# B198A.net
KiCad netlist of a schematic drawn in EAGLE
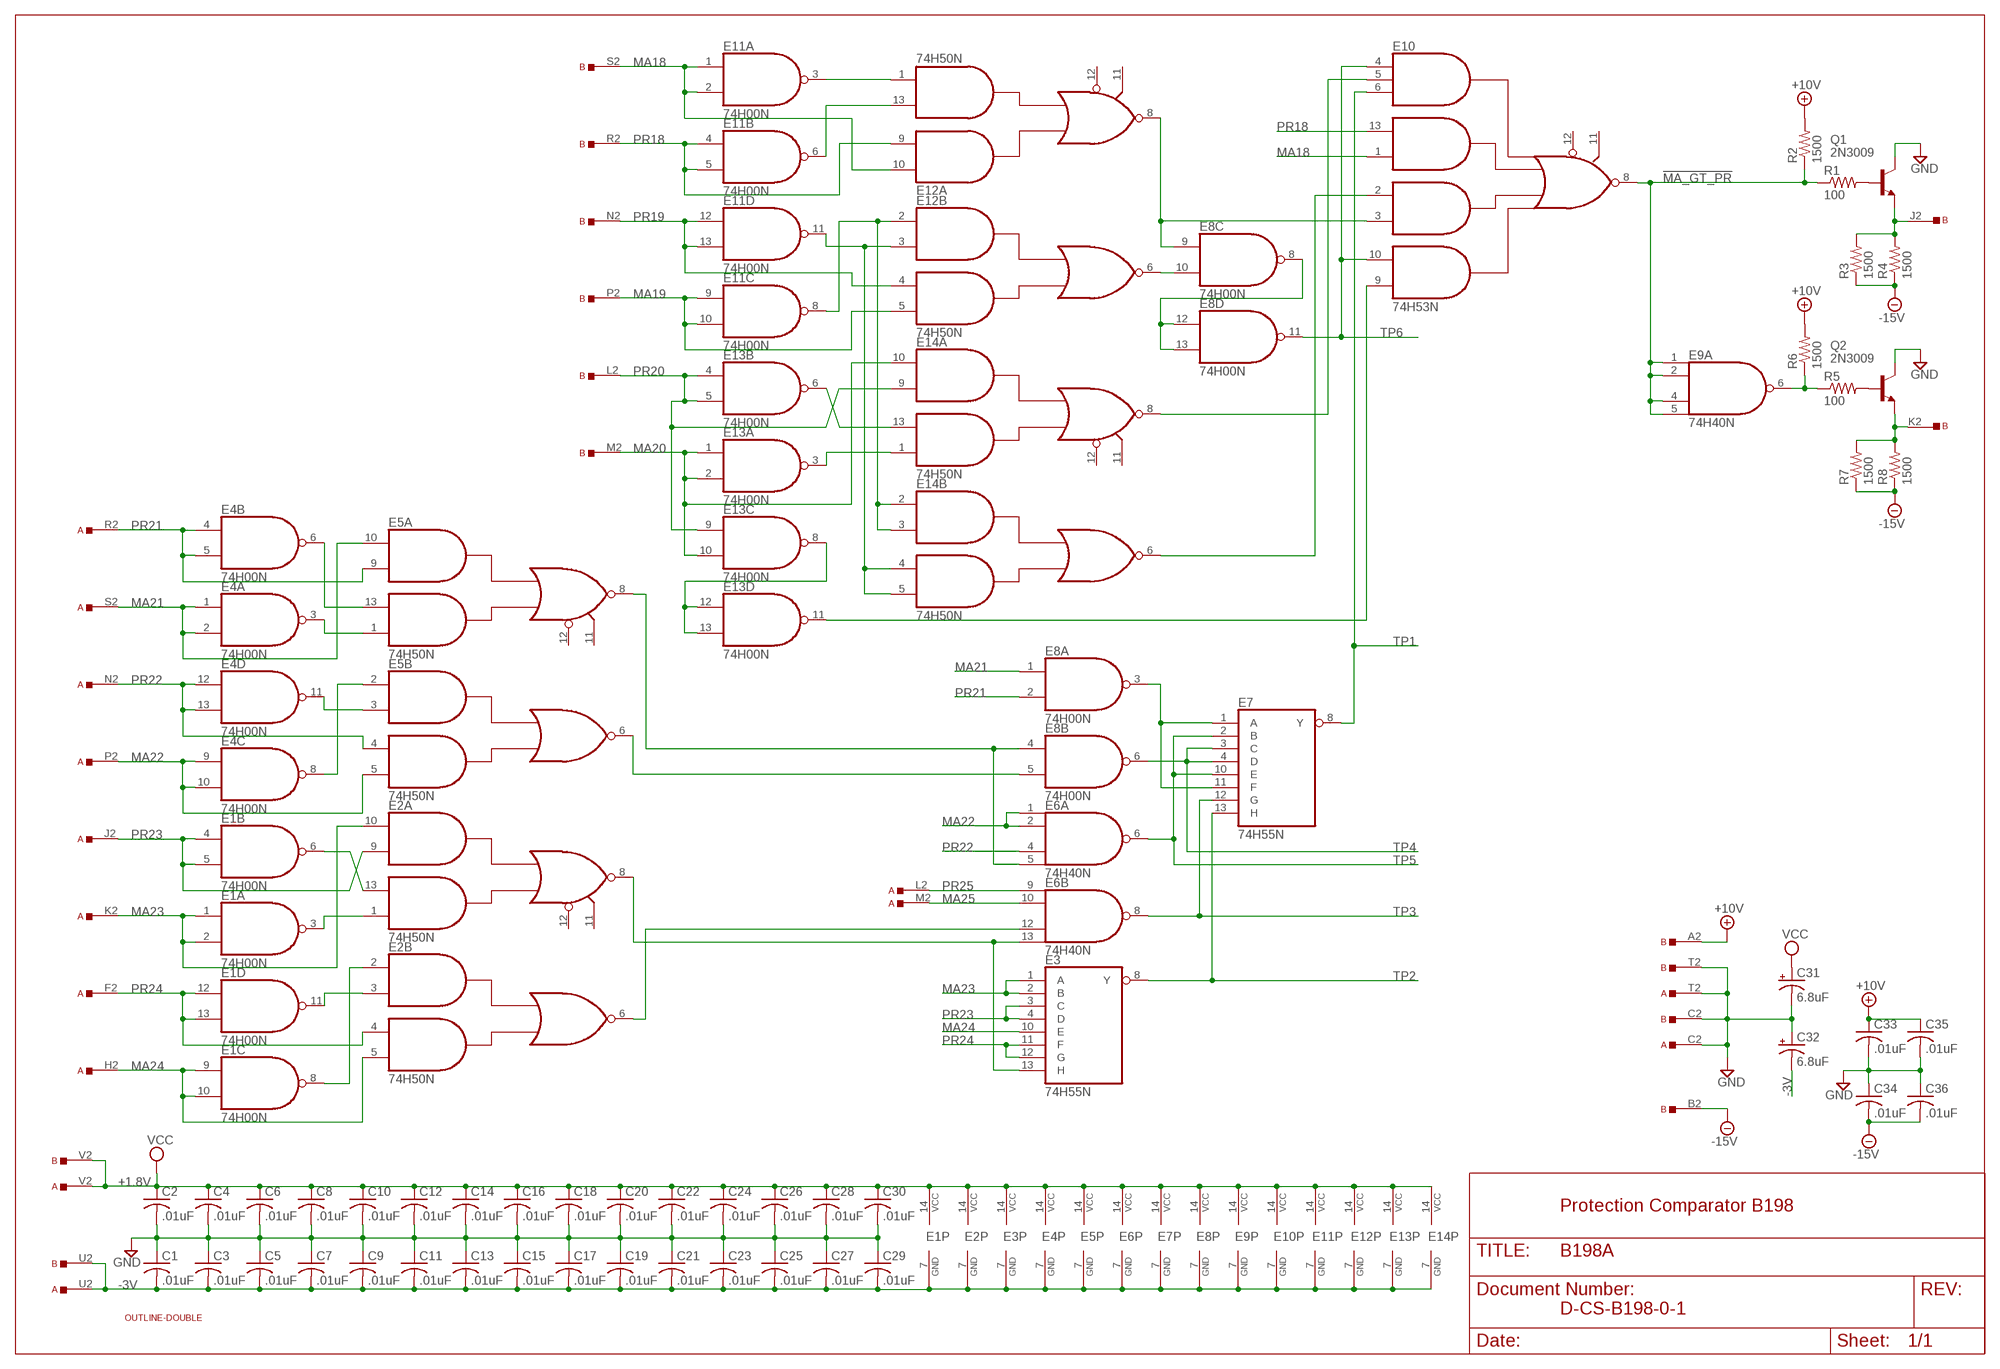
[diagram p0: schematic, sheet 1]

(export (version "E")
  (design (tool "Eeschema 10.0.6"))
  (components
    (comp (ref "A")
      (value "SS-TOP")
      (footprint "eagle-import:EDGE-CON1")
      (libsource (lib "eagle-import") (part "SS-TOP"))
    )
    (comp (ref "B")
      (value "SS-TOP")
      (footprint "eagle-import:EDGE-CON1")
      (libsource (lib "eagle-import") (part "SS-TOP"))
    )
    (comp (ref "C1")
      (value ".01uF")
      (footprint "eagle-import:C063-025X075")
      (libsource (lib "eagle-import") (part "C-US"))
    )
    (comp (ref "C2")
      (value ".01uF")
      (footprint "eagle-import:C063-025X075")
      (libsource (lib "eagle-import") (part "C-US"))
    )
    (comp (ref "C3")
      (value ".01uF")
      (footprint "eagle-import:C063-025X075")
      (libsource (lib "eagle-import") (part "C-US"))
    )
    (comp (ref "C4")
      (value ".01uF")
      (footprint "eagle-import:C063-025X075")
      (libsource (lib "eagle-import") (part "C-US"))
    )
    (comp (ref "C5")
      (value ".01uF")
      (footprint "eagle-import:C063-025X075")
      (libsource (lib "eagle-import") (part "C-US"))
    )
    (comp (ref "C6")
      (value ".01uF")
      (footprint "eagle-import:C063-025X075")
      (libsource (lib "eagle-import") (part "C-US"))
    )
    (comp (ref "C7")
      (value ".01uF")
      (footprint "eagle-import:C063-025X075")
      (libsource (lib "eagle-import") (part "C-US"))
    )
    (comp (ref "C8")
      (value ".01uF")
      (footprint "eagle-import:C063-025X075")
      (libsource (lib "eagle-import") (part "C-US"))
    )
    (comp (ref "C9")
      (value ".01uF")
      (footprint "eagle-import:C063-025X075")
      (libsource (lib "eagle-import") (part "C-US"))
    )
    (comp (ref "C10")
      (value ".01uF")
      (footprint "eagle-import:C063-025X075")
      (libsource (lib "eagle-import") (part "C-US"))
    )
    (comp (ref "C11")
      (value ".01uF")
      (footprint "eagle-import:C063-025X075")
      (libsource (lib "eagle-import") (part "C-US"))
    )
    (comp (ref "C12")
      (value ".01uF")
      (footprint "eagle-import:C063-025X075")
      (libsource (lib "eagle-import") (part "C-US"))
    )
    (comp (ref "C13")
      (value ".01uF")
      (footprint "eagle-import:C063-025X075")
      (libsource (lib "eagle-import") (part "C-US"))
    )
    (comp (ref "C14")
      (value ".01uF")
      (footprint "eagle-import:C063-025X075")
      (libsource (lib "eagle-import") (part "C-US"))
    )
    (comp (ref "C15")
      (value ".01uF")
      (footprint "eagle-import:C063-025X075")
      (libsource (lib "eagle-import") (part "C-US"))
    )
    (comp (ref "C16")
      (value ".01uF")
      (footprint "eagle-import:C063-025X075")
      (libsource (lib "eagle-import") (part "C-US"))
    )
    (comp (ref "C17")
      (value ".01uF")
      (footprint "eagle-import:C063-025X075")
      (libsource (lib "eagle-import") (part "C-US"))
    )
    (comp (ref "C18")
      (value ".01uF")
      (footprint "eagle-import:C063-025X075")
      (libsource (lib "eagle-import") (part "C-US"))
    )
    (comp (ref "C19")
      (value ".01uF")
      (footprint "eagle-import:C063-025X075")
      (libsource (lib "eagle-import") (part "C-US"))
    )
    (comp (ref "C20")
      (value ".01uF")
      (footprint "eagle-import:C063-025X075")
      (libsource (lib "eagle-import") (part "C-US"))
    )
    (comp (ref "C21")
      (value ".01uF")
      (footprint "eagle-import:C063-025X075")
      (libsource (lib "eagle-import") (part "C-US"))
    )
    (comp (ref "C22")
      (value ".01uF")
      (footprint "eagle-import:C063-025X075")
      (libsource (lib "eagle-import") (part "C-US"))
    )
    (comp (ref "C23")
      (value ".01uF")
      (footprint "eagle-import:C063-025X075")
      (libsource (lib "eagle-import") (part "C-US"))
    )
    (comp (ref "C24")
      (value ".01uF")
      (footprint "eagle-import:C063-025X075")
      (libsource (lib "eagle-import") (part "C-US"))
    )
    (comp (ref "C25")
      (value ".01uF")
      (footprint "eagle-import:C063-025X075")
      (libsource (lib "eagle-import") (part "C-US"))
    )
    (comp (ref "C26")
      (value ".01uF")
      (footprint "eagle-import:C063-025X075")
      (libsource (lib "eagle-import") (part "C-US"))
    )
    (comp (ref "C27")
      (value ".01uF")
      (footprint "eagle-import:C063-025X075")
      (libsource (lib "eagle-import") (part "C-US"))
    )
    (comp (ref "C28")
      (value ".01uF")
      (footprint "eagle-import:C063-025X075")
      (libsource (lib "eagle-import") (part "C-US"))
    )
    (comp (ref "C29")
      (value ".01uF")
      (footprint "eagle-import:C063-025X075")
      (libsource (lib "eagle-import") (part "C-US"))
    )
    (comp (ref "C30")
      (value ".01uF")
      (footprint "eagle-import:C063-025X075")
      (libsource (lib "eagle-import") (part "C-US"))
    )
    (comp (ref "C31")
      (value "6.8uF")
      (footprint "eagle-import:E15-5")
      (libsource (lib "eagle-import") (part "CPOL-USE15-5AXIAL"))
    )
    (comp (ref "C32")
      (value "6.8uF")
      (footprint "eagle-import:E15-5")
      (libsource (lib "eagle-import") (part "CPOL-USE15-5AXIAL"))
    )
    (comp (ref "C33")
      (value ".01uF")
      (footprint "eagle-import:C063-025X075")
      (libsource (lib "eagle-import") (part "C-US"))
    )
    (comp (ref "C34")
      (value ".01uF")
      (footprint "eagle-import:C063-025X075")
      (libsource (lib "eagle-import") (part "C-US"))
    )
    (comp (ref "C35")
      (value ".01uF")
      (footprint "eagle-import:C063-025X075")
      (libsource (lib "eagle-import") (part "C-US"))
    )
    (comp (ref "C36")
      (value ".01uF")
      (footprint "eagle-import:C063-025X075")
      (libsource (lib "eagle-import") (part "C-US"))
    )
    (comp (ref "E1")
      (value "74H00N")
      (footprint "eagle-import:DIL14")
      (libsource (lib "eagle-import") (part "7400NS"))
    )
    (comp (ref "E2")
      (value "74H50N")
      (footprint "eagle-import:DIL14")
      (libsource (lib "eagle-import") (part "7450N"))
    )
    (comp (ref "E3")
      (value "74H55N")
      (footprint "eagle-import:DIL14")
      (libsource (lib "eagle-import") (part "7455NLS"))
    )
    (comp (ref "E4")
      (value "74H00N")
      (footprint "eagle-import:DIL14")
      (libsource (lib "eagle-import") (part "7400NS"))
    )
    (comp (ref "E5")
      (value "74H50N")
      (footprint "eagle-import:DIL14")
      (libsource (lib "eagle-import") (part "7450N"))
    )
    (comp (ref "E6")
      (value "74H40N")
      (footprint "eagle-import:DIL14")
      (libsource (lib "eagle-import") (part "7440N"))
    )
    (comp (ref "E7")
      (value "74H55N")
      (footprint "eagle-import:DIL14")
      (libsource (lib "eagle-import") (part "7455NLS"))
    )
    (comp (ref "E8")
      (value "74H00N")
      (footprint "eagle-import:DIL14")
      (libsource (lib "eagle-import") (part "7400NS"))
    )
    (comp (ref "E9")
      (value "74H40N")
      (footprint "eagle-import:DIL14")
      (libsource (lib "eagle-import") (part "7440N"))
    )
    (comp (ref "E10")
      (value "74H53N")
      (footprint "eagle-import:DIL14")
      (libsource (lib "eagle-import") (part "74H53N"))
    )
    (comp (ref "E11")
      (value "74H00N")
      (footprint "eagle-import:DIL14")
      (libsource (lib "eagle-import") (part "7400NS"))
    )
    (comp (ref "E12")
      (value "74H50N")
      (footprint "eagle-import:DIL14")
      (libsource (lib "eagle-import") (part "7450N"))
    )
    (comp (ref "E13")
      (value "74H00N")
      (footprint "eagle-import:DIL14")
      (libsource (lib "eagle-import") (part "7400NS"))
    )
    (comp (ref "E14")
      (value "74H50N")
      (footprint "eagle-import:DIL14")
      (libsource (lib "eagle-import") (part "7450N"))
    )
    (comp (ref "Q1")
      (value "2N3009")
      (footprint "eagle-import:TO5")
      (libsource (lib "eagle-import") (part "-NPN-TO5"))
    )
    (comp (ref "Q2")
      (value "2N3009")
      (footprint "eagle-import:TO5")
      (libsource (lib "eagle-import") (part "-NPN-TO5"))
    )
    (comp (ref "R1")
      (value "100")
      (footprint "eagle-import:0207_10")
      (libsource (lib "eagle-import") (part "R-US_0207/10"))
    )
    (comp (ref "R2")
      (value "1500")
      (footprint "eagle-import:0207_10")
      (libsource (lib "eagle-import") (part "R-US_0207/10"))
    )
    (comp (ref "R3")
      (value "1500")
      (footprint "eagle-import:0207_10")
      (libsource (lib "eagle-import") (part "R-US_0207/10"))
    )
    (comp (ref "R4")
      (value "1500")
      (footprint "eagle-import:0207_10")
      (libsource (lib "eagle-import") (part "R-US_0207/10"))
    )
    (comp (ref "R5")
      (value "100")
      (footprint "eagle-import:0207_10")
      (libsource (lib "eagle-import") (part "R-US_0207/10"))
    )
    (comp (ref "R6")
      (value "1500")
      (footprint "eagle-import:0207_10")
      (libsource (lib "eagle-import") (part "R-US_0207/10"))
    )
    (comp (ref "R7")
      (value "1500")
      (footprint "eagle-import:0207_10")
      (libsource (lib "eagle-import") (part "R-US_0207/10"))
    )
    (comp (ref "R8")
      (value "1500")
      (footprint "eagle-import:0207_10")
      (libsource (lib "eagle-import") (part "R-US_0207/10"))
    )
    (comp (ref "U$1")
      (value "OUTLINE-DOUBLE")
      (footprint "eagle-import:DOUBLE")
      (libsource (lib "eagle-import") (part "OUTLINE-DOUBLE"))
    )
  )
  (nets
    (net (code "1") (name "+10V") (class "Default")
      (node (ref "B") (pin "A2") (pinfunction "P_A2") (pintype "passive"))
      (node (ref "C33") (pin "1") (pinfunction "1_1") (pintype "passive"))
      (node (ref "C35") (pin "1") (pinfunction "1_1") (pintype "passive"))
      (node (ref "R2") (pin "2") (pinfunction "2_2") (pintype "passive"))
      (node (ref "R6") (pin "2") (pinfunction "2_2") (pintype "passive"))
    )
    (net (code "2") (name "-15V") (class "Default")
      (node (ref "B") (pin "B2") (pinfunction "P_B2") (pintype "passive"))
      (node (ref "C34") (pin "2") (pinfunction "2_2") (pintype "passive"))
      (node (ref "C36") (pin "2") (pinfunction "2_2") (pintype "passive"))
      (node (ref "R3") (pin "1") (pinfunction "1_1") (pintype "passive"))
      (node (ref "R4") (pin "1") (pinfunction "1_1") (pintype "passive"))
      (node (ref "R7") (pin "1") (pinfunction "1_1") (pintype "passive"))
      (node (ref "R8") (pin "1") (pinfunction "1_1") (pintype "passive"))
    )
    (net (code "3") (name "/-3V") (class "Default")
      (node (ref "A") (pin "U2") (pinfunction "P_U2") (pintype "passive"))
      (node (ref "B") (pin "U2") (pinfunction "P_U2") (pintype "passive"))
      (node (ref "C1") (pin "2") (pinfunction "2_2") (pintype "passive"))
      (node (ref "C11") (pin "2") (pinfunction "2_2") (pintype "passive"))
      (node (ref "C13") (pin "2") (pinfunction "2_2") (pintype "passive"))
      (node (ref "C15") (pin "2") (pinfunction "2_2") (pintype "passive"))
      (node (ref "C17") (pin "2") (pinfunction "2_2") (pintype "passive"))
      (node (ref "C19") (pin "2") (pinfunction "2_2") (pintype "passive"))
      (node (ref "C21") (pin "2") (pinfunction "2_2") (pintype "passive"))
      (node (ref "C23") (pin "2") (pinfunction "2_2") (pintype "passive"))
      (node (ref "C25") (pin "2") (pinfunction "2_2") (pintype "passive"))
      (node (ref "C27") (pin "2") (pinfunction "2_2") (pintype "passive"))
      (node (ref "C29") (pin "2") (pinfunction "2_2") (pintype "passive"))
      (node (ref "C3") (pin "2") (pinfunction "2_2") (pintype "passive"))
      (node (ref "C32") (pin "-") (pinfunction "-_-") (pintype "passive"))
      (node (ref "C5") (pin "2") (pinfunction "2_2") (pintype "passive"))
      (node (ref "C7") (pin "2") (pinfunction "2_2") (pintype "passive"))
      (node (ref "C9") (pin "2") (pinfunction "2_2") (pintype "passive"))
      (node (ref "E1") (pin "7") (pinfunction "GND_7") (pintype "power_in"))
      (node (ref "E10") (pin "7") (pinfunction "GND_7") (pintype "power_in"))
      (node (ref "E11") (pin "7") (pinfunction "GND_7") (pintype "power_in"))
      (node (ref "E12") (pin "7") (pinfunction "GND_7") (pintype "power_in"))
      (node (ref "E13") (pin "7") (pinfunction "GND_7") (pintype "power_in"))
      (node (ref "E14") (pin "7") (pinfunction "GND_7") (pintype "power_in"))
      (node (ref "E2") (pin "7") (pinfunction "GND_7") (pintype "power_in"))
      (node (ref "E3") (pin "7") (pinfunction "GND_7") (pintype "power_in"))
      (node (ref "E4") (pin "7") (pinfunction "GND_7") (pintype "power_in"))
      (node (ref "E5") (pin "7") (pinfunction "GND_7") (pintype "power_in"))
      (node (ref "E6") (pin "7") (pinfunction "GND_7") (pintype "power_in"))
      (node (ref "E7") (pin "7") (pinfunction "GND_7") (pintype "power_in"))
      (node (ref "E8") (pin "7") (pinfunction "GND_7") (pintype "power_in"))
      (node (ref "E9") (pin "7") (pinfunction "GND_7") (pintype "power_in"))
    )
    (net (code "4") (name "/MA18") (class "Default")
      (node (ref "B") (pin "S2") (pinfunction "P_S2") (pintype "passive"))
      (node (ref "E10") (pin "1") (pinfunction "I4_1") (pintype "input"))
      (node (ref "E11") (pin "1") (pinfunction "I0_1") (pintype "input"))
      (node (ref "E11") (pin "2") (pinfunction "I1_2") (pintype "input"))
      (node (ref "E12") (pin "10") (pinfunction "I1_10") (pintype "input"))
    )
    (net (code "5") (name "/MA19") (class "Default")
      (node (ref "B") (pin "P2") (pinfunction "P_P2") (pintype "passive"))
      (node (ref "E11") (pin "10") (pinfunction "I1_10") (pintype "input"))
      (node (ref "E11") (pin "9") (pinfunction "I0_9") (pintype "input"))
      (node (ref "E12") (pin "5") (pinfunction "I4_5") (pintype "input"))
    )
    (net (code "6") (name "/MA20") (class "Default")
      (node (ref "B") (pin "M2") (pinfunction "P_M2") (pintype "passive"))
      (node (ref "E13") (pin "1") (pinfunction "I0_1") (pintype "input"))
      (node (ref "E13") (pin "10") (pinfunction "I1_10") (pintype "input"))
      (node (ref "E13") (pin "2") (pinfunction "I1_2") (pintype "input"))
      (node (ref "E14") (pin "10") (pinfunction "I1_10") (pintype "input"))
    )
    (net (code "7") (name "/MA21") (class "Default")
      (node (ref "A") (pin "S2") (pinfunction "P_S2") (pintype "passive"))
      (node (ref "E4") (pin "1") (pinfunction "I0_1") (pintype "input"))
      (node (ref "E4") (pin "2") (pinfunction "I1_2") (pintype "input"))
      (node (ref "E5") (pin "10") (pinfunction "I1_10") (pintype "input"))
      (node (ref "E8") (pin "1") (pinfunction "I0_1") (pintype "input"))
    )
    (net (code "8") (name "/MA22") (class "Default")
      (node (ref "A") (pin "P2") (pinfunction "P_P2") (pintype "passive"))
      (node (ref "E4") (pin "10") (pinfunction "I1_10") (pintype "input"))
      (node (ref "E4") (pin "9") (pinfunction "I0_9") (pintype "input"))
      (node (ref "E5") (pin "5") (pinfunction "I4_5") (pintype "input"))
      (node (ref "E6") (pin "1") (pinfunction "I0_1") (pintype "input"))
      (node (ref "E6") (pin "2") (pinfunction "I1_2") (pintype "input"))
    )
    (net (code "9") (name "/MA23") (class "Default")
      (node (ref "A") (pin "K2") (pinfunction "P_K2") (pintype "passive"))
      (node (ref "E1") (pin "1") (pinfunction "I0_1") (pintype "input"))
      (node (ref "E1") (pin "2") (pinfunction "I1_2") (pintype "input"))
      (node (ref "E2") (pin "10") (pinfunction "I1_10") (pintype "input"))
      (node (ref "E3") (pin "1") (pinfunction "A_1") (pintype "input"))
      (node (ref "E3") (pin "2") (pinfunction "B_2") (pintype "input"))
    )
    (net (code "10") (name "/MA24") (class "Default")
      (node (ref "A") (pin "H2") (pinfunction "P_H2") (pintype "passive"))
      (node (ref "E1") (pin "10") (pinfunction "I1_10") (pintype "input"))
      (node (ref "E1") (pin "9") (pinfunction "I0_9") (pintype "input"))
      (node (ref "E2") (pin "5") (pinfunction "I4_5") (pintype "input"))
      (node (ref "E3") (pin "10") (pinfunction "E_10") (pintype "input"))
    )
    (net (code "11") (name "/MA25") (class "Default")
      (node (ref "A") (pin "M2") (pinfunction "P_M2") (pintype "passive"))
      (node (ref "E6") (pin "10") (pinfunction "I1_10") (pintype "input"))
    )
    (net (code "12") (name "/PR18") (class "Default")
      (node (ref "B") (pin "R2") (pinfunction "P_R2") (pintype "passive"))
      (node (ref "E10") (pin "13") (pinfunction "I3_13") (pintype "input"))
      (node (ref "E11") (pin "4") (pinfunction "I0_4") (pintype "input"))
      (node (ref "E11") (pin "5") (pinfunction "I1_5") (pintype "input"))
      (node (ref "E12") (pin "9") (pinfunction "I2_9") (pintype "input"))
    )
    (net (code "13") (name "/PR19") (class "Default")
      (node (ref "B") (pin "N2") (pinfunction "P_N2") (pintype "passive"))
      (node (ref "E11") (pin "12") (pinfunction "I0_12") (pintype "input"))
      (node (ref "E11") (pin "13") (pinfunction "I1_13") (pintype "input"))
      (node (ref "E12") (pin "4") (pinfunction "I3_4") (pintype "input"))
    )
    (net (code "14") (name "/PR20") (class "Default")
      (node (ref "B") (pin "L2") (pinfunction "P_L2") (pintype "passive"))
      (node (ref "E13") (pin "4") (pinfunction "I0_4") (pintype "input"))
      (node (ref "E13") (pin "5") (pinfunction "I1_5") (pintype "input"))
      (node (ref "E13") (pin "9") (pinfunction "I0_9") (pintype "input"))
      (node (ref "E14") (pin "9") (pinfunction "I2_9") (pintype "input"))
    )
    (net (code "15") (name "/PR21") (class "Default")
      (node (ref "A") (pin "R2") (pinfunction "P_R2") (pintype "passive"))
      (node (ref "E4") (pin "4") (pinfunction "I0_4") (pintype "input"))
      (node (ref "E4") (pin "5") (pinfunction "I1_5") (pintype "input"))
      (node (ref "E5") (pin "9") (pinfunction "I2_9") (pintype "input"))
      (node (ref "E8") (pin "2") (pinfunction "I1_2") (pintype "input"))
    )
    (net (code "16") (name "/PR22") (class "Default")
      (node (ref "A") (pin "N2") (pinfunction "P_N2") (pintype "passive"))
      (node (ref "E4") (pin "12") (pinfunction "I0_12") (pintype "input"))
      (node (ref "E4") (pin "13") (pinfunction "I1_13") (pintype "input"))
      (node (ref "E5") (pin "4") (pinfunction "I3_4") (pintype "input"))
      (node (ref "E6") (pin "4") (pinfunction "I2_4") (pintype "input"))
    )
    (net (code "17") (name "/PR23") (class "Default")
      (node (ref "A") (pin "J2") (pinfunction "P_J2") (pintype "passive"))
      (node (ref "E1") (pin "4") (pinfunction "I0_4") (pintype "input"))
      (node (ref "E1") (pin "5") (pinfunction "I1_5") (pintype "input"))
      (node (ref "E2") (pin "9") (pinfunction "I2_9") (pintype "input"))
      (node (ref "E3") (pin "3") (pinfunction "C_3") (pintype "input"))
      (node (ref "E3") (pin "4") (pinfunction "D_4") (pintype "input"))
    )
    (net (code "18") (name "/PR24") (class "Default")
      (node (ref "A") (pin "F2") (pinfunction "P_F2") (pintype "passive"))
      (node (ref "E1") (pin "12") (pinfunction "I0_12") (pintype "input"))
      (node (ref "E1") (pin "13") (pinfunction "I1_13") (pintype "input"))
      (node (ref "E2") (pin "4") (pinfunction "I3_4") (pintype "input"))
      (node (ref "E3") (pin "11") (pinfunction "F_11") (pintype "input"))
      (node (ref "E3") (pin "12") (pinfunction "G_12") (pintype "input"))
    )
    (net (code "19") (name "/PR25") (class "Default")
      (node (ref "A") (pin "L2") (pinfunction "P_L2") (pintype "passive"))
      (node (ref "E6") (pin "9") (pinfunction "I0_9") (pintype "input"))
    )
    (net (code "20") (name "/TP1") (class "Default")
      (node (ref "E10") (pin "6") (pinfunction "I2_6") (pintype "input"))
      (node (ref "E7") (pin "8") (pinfunction "Y_8") (pintype "output"))
    )
    (net (code "21") (name "/TP2") (class "Default")
      (node (ref "E3") (pin "8") (pinfunction "Y_8") (pintype "output"))
      (node (ref "E7") (pin "13") (pinfunction "H_13") (pintype "input"))
    )
    (net (code "22") (name "/TP3") (class "Default")
      (node (ref "E6") (pin "8") (pinfunction "O_8") (pintype "output"))
      (node (ref "E7") (pin "12") (pinfunction "G_12") (pintype "input"))
    )
    (net (code "23") (name "/TP4") (class "Default")
      (node (ref "E7") (pin "3") (pinfunction "C_3") (pintype "input"))
      (node (ref "E7") (pin "4") (pinfunction "D_4") (pintype "input"))
      (node (ref "E8") (pin "6") (pinfunction "O_6") (pintype "output"))
    )
    (net (code "24") (name "/TP5") (class "Default")
      (node (ref "E6") (pin "6") (pinfunction "O_6") (pintype "output"))
      (node (ref "E7") (pin "10") (pinfunction "E_10") (pintype "input"))
      (node (ref "E7") (pin "2") (pinfunction "B_2") (pintype "input"))
    )
    (net (code "25") (name "/TP6") (class "Default")
      (node (ref "E10") (pin "10") (pinfunction "I7_10") (pintype "input"))
      (node (ref "E10") (pin "4") (pinfunction "I1_4") (pintype "input"))
      (node (ref "E8") (pin "11") (pinfunction "O_11") (pintype "output"))
    )
    (net (code "26") (name "/~{MA_GT_PR}") (class "Default")
      (node (ref "E10") (pin "8") (pinfunction "O_8") (pintype "output"))
      (node (ref "E9") (pin "1") (pinfunction "I0_1") (pintype "input"))
      (node (ref "E9") (pin "2") (pinfunction "I1_2") (pintype "input"))
      (node (ref "E9") (pin "4") (pinfunction "I2_4") (pintype "input"))
      (node (ref "E9") (pin "5") (pinfunction "I3_5") (pintype "input"))
      (node (ref "R1") (pin "1") (pinfunction "1_1") (pintype "passive"))
      (node (ref "R2") (pin "1") (pinfunction "1_1") (pintype "passive"))
    )
    (net (code "27") (name "GND") (class "Default")
      (node (ref "A") (pin "C2") (pinfunction "P_C2") (pintype "passive"))
      (node (ref "A") (pin "T2") (pinfunction "P_T2") (pintype "passive"))
      (node (ref "B") (pin "C2") (pinfunction "P_C2") (pintype "passive"))
      (node (ref "B") (pin "T2") (pinfunction "P_T2") (pintype "passive"))
      (node (ref "C1") (pin "1") (pinfunction "1_1") (pintype "passive"))
      (node (ref "C10") (pin "2") (pinfunction "2_2") (pintype "passive"))
      (node (ref "C11") (pin "1") (pinfunction "1_1") (pintype "passive"))
      (node (ref "C12") (pin "2") (pinfunction "2_2") (pintype "passive"))
      (node (ref "C13") (pin "1") (pinfunction "1_1") (pintype "passive"))
      (node (ref "C14") (pin "2") (pinfunction "2_2") (pintype "passive"))
      (node (ref "C15") (pin "1") (pinfunction "1_1") (pintype "passive"))
      (node (ref "C16") (pin "2") (pinfunction "2_2") (pintype "passive"))
      (node (ref "C17") (pin "1") (pinfunction "1_1") (pintype "passive"))
      (node (ref "C18") (pin "2") (pinfunction "2_2") (pintype "passive"))
      (node (ref "C19") (pin "1") (pinfunction "1_1") (pintype "passive"))
      (node (ref "C2") (pin "2") (pinfunction "2_2") (pintype "passive"))
      (node (ref "C20") (pin "2") (pinfunction "2_2") (pintype "passive"))
      (node (ref "C21") (pin "1") (pinfunction "1_1") (pintype "passive"))
      (node (ref "C22") (pin "2") (pinfunction "2_2") (pintype "passive"))
      (node (ref "C23") (pin "1") (pinfunction "1_1") (pintype "passive"))
      (node (ref "C24") (pin "2") (pinfunction "2_2") (pintype "passive"))
      (node (ref "C25") (pin "1") (pinfunction "1_1") (pintype "passive"))
      (node (ref "C26") (pin "2") (pinfunction "2_2") (pintype "passive"))
      (node (ref "C27") (pin "1") (pinfunction "1_1") (pintype "passive"))
      (node (ref "C28") (pin "2") (pinfunction "2_2") (pintype "passive"))
      (node (ref "C29") (pin "1") (pinfunction "1_1") (pintype "passive"))
      (node (ref "C3") (pin "1") (pinfunction "1_1") (pintype "passive"))
      (node (ref "C30") (pin "2") (pinfunction "2_2") (pintype "passive"))
      (node (ref "C31") (pin "-") (pinfunction "-_-") (pintype "passive"))
      (node (ref "C32") (pin "+") (pinfunction "+_+") (pintype "passive"))
      (node (ref "C33") (pin "2") (pinfunction "2_2") (pintype "passive"))
      (node (ref "C34") (pin "1") (pinfunction "1_1") (pintype "passive"))
      (node (ref "C35") (pin "2") (pinfunction "2_2") (pintype "passive"))
      (node (ref "C36") (pin "1") (pinfunction "1_1") (pintype "passive"))
      (node (ref "C4") (pin "2") (pinfunction "2_2") (pintype "passive"))
      (node (ref "C5") (pin "1") (pinfunction "1_1") (pintype "passive"))
      (node (ref "C6") (pin "2") (pinfunction "2_2") (pintype "passive"))
      (node (ref "C7") (pin "1") (pinfunction "1_1") (pintype "passive"))
      (node (ref "C8") (pin "2") (pinfunction "2_2") (pintype "passive"))
      (node (ref "C9") (pin "1") (pinfunction "1_1") (pintype "passive"))
      (node (ref "Q1") (pin "3") (pinfunction "C_3") (pintype "passive"))
      (node (ref "Q2") (pin "3") (pinfunction "C_3") (pintype "passive"))
    )
    (net (code "28") (name "Net-(BH-P)") (class "Default")
      (node (ref "B") (pin "J2") (pinfunction "P_J2") (pintype "passive"))
      (node (ref "Q1") (pin "1") (pinfunction "E_1") (pintype "passive"))
      (node (ref "R3") (pin "2") (pinfunction "2_2") (pintype "passive"))
      (node (ref "R4") (pin "2") (pinfunction "2_2") (pintype "passive"))
    )
    (net (code "29") (name "Net-(BI-P)") (class "Default")
      (node (ref "B") (pin "K2") (pinfunction "P_K2") (pintype "passive"))
      (node (ref "Q2") (pin "1") (pinfunction "E_1") (pintype "passive"))
      (node (ref "R7") (pin "2") (pinfunction "2_2") (pintype "passive"))
      (node (ref "R8") (pin "2") (pinfunction "2_2") (pintype "passive"))
    )
    (net (code "30") (name "Net-(E1A-O)") (class "Default")
      (node (ref "E1") (pin "3") (pinfunction "O_3") (pintype "output"))
      (node (ref "E2") (pin "1") (pinfunction "I4_1") (pintype "input"))
    )
    (net (code "31") (name "Net-(E1B-O)") (class "Default")
      (node (ref "E1") (pin "6") (pinfunction "O_6") (pintype "output"))
      (node (ref "E2") (pin "13") (pinfunction "I3_13") (pintype "input"))
    )
    (net (code "32") (name "Net-(E1C-O)") (class "Default")
      (node (ref "E1") (pin "8") (pinfunction "O_8") (pintype "output"))
      (node (ref "E2") (pin "2") (pinfunction "I1_2") (pintype "input"))
    )
    (net (code "33") (name "Net-(E1D-O)") (class "Default")
      (node (ref "E1") (pin "11") (pinfunction "O_11") (pintype "output"))
      (node (ref "E2") (pin "3") (pinfunction "I2_3") (pintype "input"))
    )
    (net (code "34") (name "Net-(E2A-O)") (class "Default")
      (node (ref "E2") (pin "8") (pinfunction "O_8") (pintype "output"))
      (node (ref "E3") (pin "13") (pinfunction "H_13") (pintype "input"))
      (node (ref "E6") (pin "13") (pinfunction "I3_13") (pintype "input"))
    )
    (net (code "35") (name "Net-(E2B-O)") (class "Default")
      (node (ref "E2") (pin "6") (pinfunction "O_6") (pintype "output"))
      (node (ref "E6") (pin "12") (pinfunction "I2_12") (pintype "input"))
    )
    (net (code "36") (name "Net-(E4A-O)") (class "Default")
      (node (ref "E4") (pin "3") (pinfunction "O_3") (pintype "output"))
      (node (ref "E5") (pin "1") (pinfunction "I4_1") (pintype "input"))
    )
    (net (code "37") (name "Net-(E4B-O)") (class "Default")
      (node (ref "E4") (pin "6") (pinfunction "O_6") (pintype "output"))
      (node (ref "E5") (pin "13") (pinfunction "I3_13") (pintype "input"))
    )
    (net (code "38") (name "Net-(E4C-O)") (class "Default")
      (node (ref "E4") (pin "8") (pinfunction "O_8") (pintype "output"))
      (node (ref "E5") (pin "2") (pinfunction "I1_2") (pintype "input"))
    )
    (net (code "39") (name "Net-(E4D-O)") (class "Default")
      (node (ref "E4") (pin "11") (pinfunction "O_11") (pintype "output"))
      (node (ref "E5") (pin "3") (pinfunction "I2_3") (pintype "input"))
    )
    (net (code "40") (name "Net-(E5A-O)") (class "Default")
      (node (ref "E5") (pin "8") (pinfunction "O_8") (pintype "output"))
      (node (ref "E6") (pin "5") (pinfunction "I3_5") (pintype "input"))
      (node (ref "E8") (pin "4") (pinfunction "I0_4") (pintype "input"))
    )
    (net (code "41") (name "Net-(E5B-O)") (class "Default")
      (node (ref "E5") (pin "6") (pinfunction "O_6") (pintype "output"))
      (node (ref "E8") (pin "5") (pinfunction "I1_5") (pintype "input"))
    )
    (net (code "42") (name "Net-(E7A-A)") (class "Default")
      (node (ref "E7") (pin "1") (pinfunction "A_1") (pintype "input"))
      (node (ref "E7") (pin "11") (pinfunction "F_11") (pintype "input"))
      (node (ref "E8") (pin "3") (pinfunction "O_3") (pintype "output"))
    )
    (net (code "43") (name "Net-(E8C-O)") (class "Default")
      (node (ref "E8") (pin "12") (pinfunction "I0_12") (pintype "input"))
      (node (ref "E8") (pin "13") (pinfunction "I1_13") (pintype "input"))
      (node (ref "E8") (pin "8") (pinfunction "O_8") (pintype "output"))
    )
    (net (code "44") (name "Net-(E9C-O)") (class "Default")
      (node (ref "E9") (pin "6") (pinfunction "O_6") (pintype "output"))
      (node (ref "R5") (pin "1") (pinfunction "1_1") (pintype "passive"))
      (node (ref "R6") (pin "1") (pinfunction "1_1") (pintype "passive"))
    )
    (net (code "45") (name "Net-(E10A-I5)") (class "Default")
      (node (ref "E10") (pin "2") (pinfunction "I5_2") (pintype "input"))
      (node (ref "E14") (pin "6") (pinfunction "O_6") (pintype "output"))
    )
    (net (code "46") (name "Net-(E10A-I6)") (class "Default")
      (node (ref "E10") (pin "3") (pinfunction "I6_3") (pintype "input"))
      (node (ref "E12") (pin "8") (pinfunction "O_8") (pintype "output"))
      (node (ref "E8") (pin "9") (pinfunction "I0_9") (pintype "input"))
    )
    (net (code "47") (name "Net-(E10A-I8)") (class "Default")
      (node (ref "E10") (pin "9") (pinfunction "I8_9") (pintype "input"))
      (node (ref "E13") (pin "11") (pinfunction "O_11") (pintype "output"))
    )
    (net (code "48") (name "Net-(E10A-I11)") (class "Default")
      (node (ref "E10") (pin "5") (pinfunction "I11_5") (pintype "input"))
      (node (ref "E14") (pin "8") (pinfunction "O_8") (pintype "output"))
    )
    (net (code "49") (name "Net-(E11A-O)") (class "Default")
      (node (ref "E11") (pin "3") (pinfunction "O_3") (pintype "output"))
      (node (ref "E12") (pin "1") (pinfunction "I4_1") (pintype "input"))
    )
    (net (code "50") (name "Net-(E11B-O)") (class "Default")
      (node (ref "E11") (pin "6") (pinfunction "O_6") (pintype "output"))
      (node (ref "E12") (pin "13") (pinfunction "I3_13") (pintype "input"))
    )
    (net (code "51") (name "Net-(E11C-O)") (class "Default")
      (node (ref "E11") (pin "8") (pinfunction "O_8") (pintype "output"))
      (node (ref "E12") (pin "2") (pinfunction "I1_2") (pintype "input"))
      (node (ref "E14") (pin "2") (pinfunction "I1_2") (pintype "input"))
      (node (ref "E14") (pin "3") (pinfunction "I2_3") (pintype "input"))
    )
    (net (code "52") (name "Net-(E11D-O)") (class "Default")
      (node (ref "E11") (pin "11") (pinfunction "O_11") (pintype "output"))
      (node (ref "E12") (pin "3") (pinfunction "I2_3") (pintype "input"))
      (node (ref "E14") (pin "4") (pinfunction "I3_4") (pintype "input"))
      (node (ref "E14") (pin "5") (pinfunction "I4_5") (pintype "input"))
    )
    (net (code "53") (name "Net-(E12B-O)") (class "Default")
      (node (ref "E12") (pin "6") (pinfunction "O_6") (pintype "output"))
      (node (ref "E8") (pin "10") (pinfunction "I1_10") (pintype "input"))
    )
    (net (code "54") (name "Net-(E13A-O)") (class "Default")
      (node (ref "E13") (pin "3") (pinfunction "O_3") (pintype "output"))
      (node (ref "E14") (pin "1") (pinfunction "I4_1") (pintype "input"))
    )
    (net (code "55") (name "Net-(E13B-O)") (class "Default")
      (node (ref "E13") (pin "6") (pinfunction "O_6") (pintype "output"))
      (node (ref "E14") (pin "13") (pinfunction "I3_13") (pintype "input"))
    )
    (net (code "56") (name "Net-(E13C-O)") (class "Default")
      (node (ref "E13") (pin "12") (pinfunction "I0_12") (pintype "input"))
      (node (ref "E13") (pin "13") (pinfunction "I1_13") (pintype "input"))
      (node (ref "E13") (pin "8") (pinfunction "O_8") (pintype "output"))
    )
    (net (code "57") (name "Net-(Q1-B)") (class "Default")
      (node (ref "Q1") (pin "2") (pinfunction "B_2") (pintype "passive"))
      (node (ref "R1") (pin "2") (pinfunction "2_2") (pintype "passive"))
    )
    (net (code "58") (name "Net-(Q2-B)") (class "Default")
      (node (ref "Q2") (pin "2") (pinfunction "B_2") (pintype "passive"))
      (node (ref "R5") (pin "2") (pinfunction "2_2") (pintype "passive"))
    )
    (net (code "59") (name "VCC") (class "Default")
      (node (ref "A") (pin "V2") (pinfunction "P_V2") (pintype "passive"))
      (node (ref "B") (pin "V2") (pinfunction "P_V2") (pintype "passive"))
      (node (ref "C10") (pin "1") (pinfunction "1_1") (pintype "passive"))
      (node (ref "C12") (pin "1") (pinfunction "1_1") (pintype "passive"))
      (node (ref "C14") (pin "1") (pinfunction "1_1") (pintype "passive"))
      (node (ref "C16") (pin "1") (pinfunction "1_1") (pintype "passive"))
      (node (ref "C18") (pin "1") (pinfunction "1_1") (pintype "passive"))
      (node (ref "C2") (pin "1") (pinfunction "1_1") (pintype "passive"))
      (node (ref "C20") (pin "1") (pinfunction "1_1") (pintype "passive"))
      (node (ref "C22") (pin "1") (pinfunction "1_1") (pintype "passive"))
      (node (ref "C24") (pin "1") (pinfunction "1_1") (pintype "passive"))
      (node (ref "C26") (pin "1") (pinfunction "1_1") (pintype "passive"))
      (node (ref "C28") (pin "1") (pinfunction "1_1") (pintype "passive"))
      (node (ref "C30") (pin "1") (pinfunction "1_1") (pintype "passive"))
      (node (ref "C31") (pin "+") (pinfunction "+_+") (pintype "passive"))
      (node (ref "C4") (pin "1") (pinfunction "1_1") (pintype "passive"))
      (node (ref "C6") (pin "1") (pinfunction "1_1") (pintype "passive"))
      (node (ref "C8") (pin "1") (pinfunction "1_1") (pintype "passive"))
      (node (ref "E1") (pin "14") (pinfunction "VCC_14") (pintype "power_in"))
      (node (ref "E10") (pin "14") (pinfunction "VCC_14") (pintype "power_in"))
      (node (ref "E11") (pin "14") (pinfunction "VCC_14") (pintype "power_in"))
      (node (ref "E12") (pin "14") (pinfunction "VCC_14") (pintype "power_in"))
      (node (ref "E13") (pin "14") (pinfunction "VCC_14") (pintype "power_in"))
      (node (ref "E14") (pin "14") (pinfunction "VCC_14") (pintype "power_in"))
      (node (ref "E2") (pin "14") (pinfunction "VCC_14") (pintype "power_in"))
      (node (ref "E3") (pin "14") (pinfunction "VCC_14") (pintype "power_in"))
      (node (ref "E4") (pin "14") (pinfunction "VCC_14") (pintype "power_in"))
      (node (ref "E5") (pin "14") (pinfunction "VCC_14") (pintype "power_in"))
      (node (ref "E6") (pin "14") (pinfunction "VCC_14") (pintype "power_in"))
      (node (ref "E7") (pin "14") (pinfunction "VCC_14") (pintype "power_in"))
      (node (ref "E8") (pin "14") (pinfunction "VCC_14") (pintype "power_in"))
      (node (ref "E9") (pin "14") (pinfunction "VCC_14") (pintype "power_in"))
    )
    (net (code "60") (name "unconnected-(E2A-I5-Pad12)") (class "Default")
      (node (ref "E2") (pin "12") (pinfunction "I5_12") (pintype "passive"))
    )
    (net (code "61") (name "unconnected-(E2A-I6-Pad11)") (class "Default")
      (node (ref "E2") (pin "11") (pinfunction "I6_11") (pintype "passive"))
    )
    (net (code "62") (name "unconnected-(E5A-I5-Pad12)") (class "Default")
      (node (ref "E5") (pin "12") (pinfunction "I5_12") (pintype "passive"))
    )
    (net (code "63") (name "unconnected-(E5A-I6-Pad11)") (class "Default")
      (node (ref "E5") (pin "11") (pinfunction "I6_11") (pintype "passive"))
    )
    (net (code "64") (name "unconnected-(E10A-I9-Pad12)") (class "Default")
      (node (ref "E10") (pin "12") (pinfunction "I9_12") (pintype "passive"))
    )
    (net (code "65") (name "unconnected-(E10A-I10-Pad11)") (class "Default")
      (node (ref "E10") (pin "11") (pinfunction "I10_11") (pintype "passive"))
    )
    (net (code "66") (name "unconnected-(E12A-I5-Pad12)") (class "Default")
      (node (ref "E12") (pin "12") (pinfunction "I5_12") (pintype "passive"))
    )
    (net (code "67") (name "unconnected-(E12A-I6-Pad11)") (class "Default")
      (node (ref "E12") (pin "11") (pinfunction "I6_11") (pintype "passive"))
    )
    (net (code "68") (name "unconnected-(E14A-I5-Pad12)") (class "Default")
      (node (ref "E14") (pin "12") (pinfunction "I5_12") (pintype "passive"))
    )
    (net (code "69") (name "unconnected-(E14A-I6-Pad11)") (class "Default")
      (node (ref "E14") (pin "11") (pinfunction "I6_11") (pintype "passive"))
    )
  )
)
